# HAP-12xBusverteiler-1_0.net
KiCad netlist of a schematic drawn in EAGLE
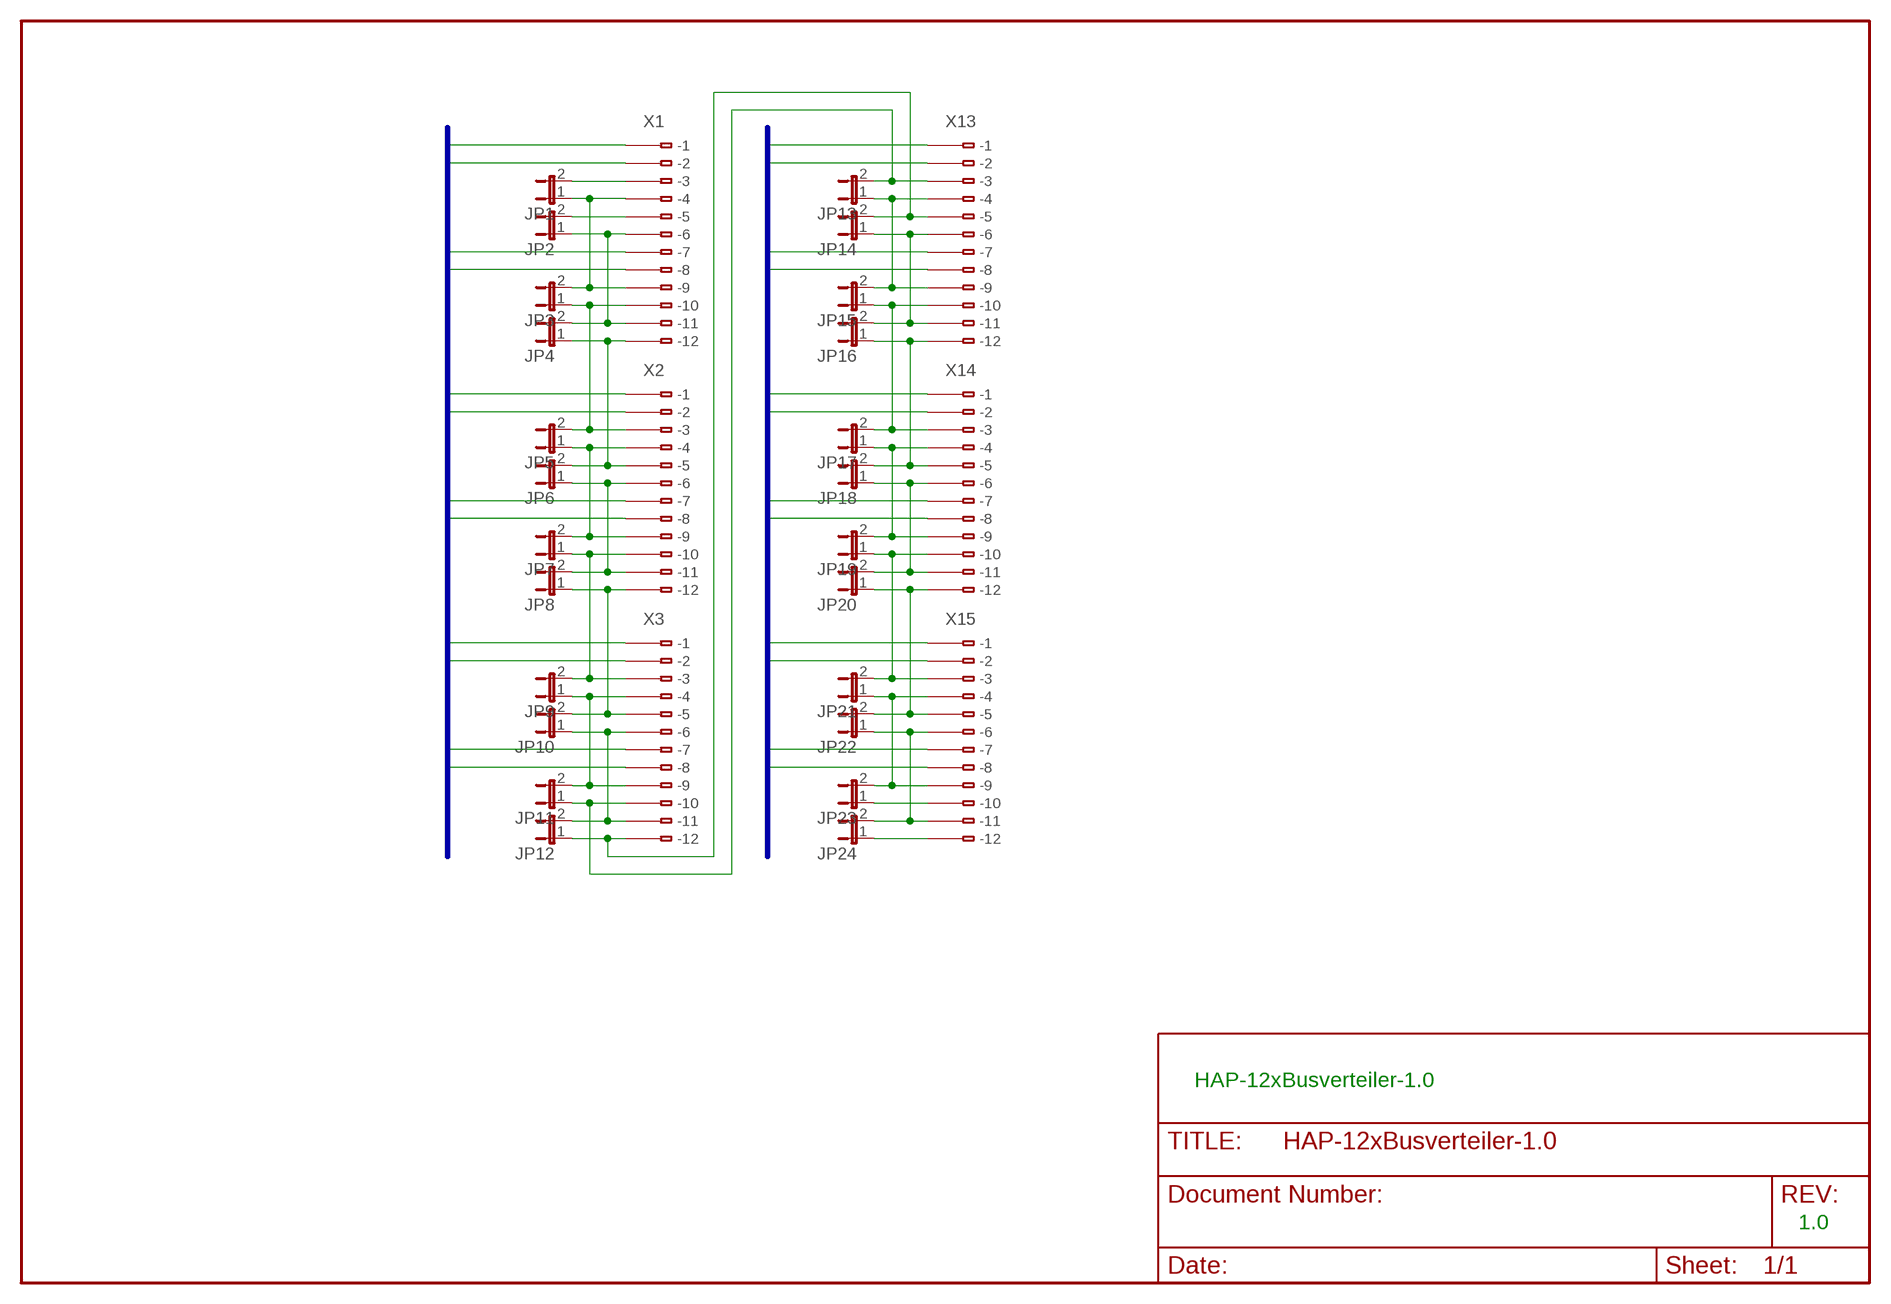
[diagram p0: schematic, sheet 1]

(export (version "E")
  (design (tool "Eeschema 10.0.6"))
  (components
    (comp (ref "JP1")
      (value "JP1E")
      (footprint "eagle-import:JP1")
      (libsource (lib "eagle-import") (part "JP1E"))
    )
    (comp (ref "JP2")
      (value "JP1E")
      (footprint "eagle-import:JP1")
      (libsource (lib "eagle-import") (part "JP1E"))
    )
    (comp (ref "JP3")
      (value "JP1E")
      (footprint "eagle-import:JP1")
      (libsource (lib "eagle-import") (part "JP1E"))
    )
    (comp (ref "JP4")
      (value "JP1E")
      (footprint "eagle-import:JP1")
      (libsource (lib "eagle-import") (part "JP1E"))
    )
    (comp (ref "JP5")
      (value "JP1E")
      (footprint "eagle-import:JP1")
      (libsource (lib "eagle-import") (part "JP1E"))
    )
    (comp (ref "JP6")
      (value "JP1E")
      (footprint "eagle-import:JP1")
      (libsource (lib "eagle-import") (part "JP1E"))
    )
    (comp (ref "JP7")
      (value "JP1E")
      (footprint "eagle-import:JP1")
      (libsource (lib "eagle-import") (part "JP1E"))
    )
    (comp (ref "JP8")
      (value "JP1E")
      (footprint "eagle-import:JP1")
      (libsource (lib "eagle-import") (part "JP1E"))
    )
    (comp (ref "JP9")
      (value "JP1E")
      (footprint "eagle-import:JP1")
      (libsource (lib "eagle-import") (part "JP1E"))
    )
    (comp (ref "JP10")
      (value "JP1E")
      (footprint "eagle-import:JP1")
      (libsource (lib "eagle-import") (part "JP1E"))
    )
    (comp (ref "JP11")
      (value "JP1E")
      (footprint "eagle-import:JP1")
      (libsource (lib "eagle-import") (part "JP1E"))
    )
    (comp (ref "JP12")
      (value "JP1E")
      (footprint "eagle-import:JP1")
      (libsource (lib "eagle-import") (part "JP1E"))
    )
    (comp (ref "JP13")
      (value "JP1E")
      (footprint "eagle-import:JP1")
      (libsource (lib "eagle-import") (part "JP1E"))
    )
    (comp (ref "JP14")
      (value "JP1E")
      (footprint "eagle-import:JP1")
      (libsource (lib "eagle-import") (part "JP1E"))
    )
    (comp (ref "JP15")
      (value "JP1E")
      (footprint "eagle-import:JP1")
      (libsource (lib "eagle-import") (part "JP1E"))
    )
    (comp (ref "JP16")
      (value "JP1E")
      (footprint "eagle-import:JP1")
      (libsource (lib "eagle-import") (part "JP1E"))
    )
    (comp (ref "JP17")
      (value "JP1E")
      (footprint "eagle-import:JP1")
      (libsource (lib "eagle-import") (part "JP1E"))
    )
    (comp (ref "JP18")
      (value "JP1E")
      (footprint "eagle-import:JP1")
      (libsource (lib "eagle-import") (part "JP1E"))
    )
    (comp (ref "JP19")
      (value "JP1E")
      (footprint "eagle-import:JP1")
      (libsource (lib "eagle-import") (part "JP1E"))
    )
    (comp (ref "JP20")
      (value "JP1E")
      (footprint "eagle-import:JP1")
      (libsource (lib "eagle-import") (part "JP1E"))
    )
    (comp (ref "JP21")
      (value "JP1E")
      (footprint "eagle-import:JP1")
      (libsource (lib "eagle-import") (part "JP1E"))
    )
    (comp (ref "JP22")
      (value "JP1E")
      (footprint "eagle-import:JP1")
      (libsource (lib "eagle-import") (part "JP1E"))
    )
    (comp (ref "JP23")
      (value "JP1E")
      (footprint "eagle-import:JP1")
      (libsource (lib "eagle-import") (part "JP1E"))
    )
    (comp (ref "JP24")
      (value "JP1E")
      (footprint "eagle-import:JP1")
      (libsource (lib "eagle-import") (part "JP1E"))
    )
    (comp (ref "X1")
      (value "233-512")
      (footprint "eagle-import:233-512")
      (fields (field (name "MF") "Wago Corporation") (field (name "MPN") "0233-0512"))
      (libsource (lib "eagle-import") (part "233-512"))
    )
    (comp (ref "X2")
      (value "233-512")
      (footprint "eagle-import:233-512")
      (fields (field (name "MF") "Wago Corporation") (field (name "MPN") "0233-0512"))
      (libsource (lib "eagle-import") (part "233-512"))
    )
    (comp (ref "X3")
      (value "233-512")
      (footprint "eagle-import:233-512")
      (fields (field (name "MF") "Wago Corporation") (field (name "MPN") "0233-0512"))
      (libsource (lib "eagle-import") (part "233-512"))
    )
    (comp (ref "X13")
      (value "233-512")
      (footprint "eagle-import:233-512")
      (fields (field (name "MF") "Wago Corporation") (field (name "MPN") "0233-0512"))
      (libsource (lib "eagle-import") (part "233-512"))
    )
    (comp (ref "X14")
      (value "233-512")
      (footprint "eagle-import:233-512")
      (fields (field (name "MF") "Wago Corporation") (field (name "MPN") "0233-0512"))
      (libsource (lib "eagle-import") (part "233-512"))
    )
    (comp (ref "X15")
      (value "233-512")
      (footprint "eagle-import:233-512")
      (fields (field (name "MF") "Wago Corporation") (field (name "MPN") "0233-0512"))
      (libsource (lib "eagle-import") (part "233-512"))
    )
  )
  (nets
    (net (code "1") (name "/12V") (class "Default")
      (node (ref "X1") (pin "B1") (pinfunction "B-1_B1") (pintype "passive"))
      (node (ref "X1") (pin "B7") (pinfunction "B-7_B7") (pintype "passive"))
      (node (ref "X13") (pin "B1") (pinfunction "B-1_B1") (pintype "passive"))
      (node (ref "X13") (pin "B7") (pinfunction "B-7_B7") (pintype "passive"))
      (node (ref "X14") (pin "B1") (pinfunction "B-1_B1") (pintype "passive"))
      (node (ref "X14") (pin "B7") (pinfunction "B-7_B7") (pintype "passive"))
      (node (ref "X15") (pin "B1") (pinfunction "B-1_B1") (pintype "passive"))
      (node (ref "X15") (pin "B7") (pinfunction "B-7_B7") (pintype "passive"))
      (node (ref "X2") (pin "B1") (pinfunction "B-1_B1") (pintype "passive"))
      (node (ref "X2") (pin "B7") (pinfunction "B-7_B7") (pintype "passive"))
      (node (ref "X3") (pin "B1") (pinfunction "B-1_B1") (pintype "passive"))
      (node (ref "X3") (pin "B7") (pinfunction "B-7_B7") (pintype "passive"))
    )
    (net (code "2") (name "/GND") (class "Default")
      (node (ref "X1") (pin "B2") (pinfunction "B-2_B2") (pintype "passive"))
      (node (ref "X1") (pin "B8") (pinfunction "B-8_B8") (pintype "passive"))
      (node (ref "X13") (pin "B2") (pinfunction "B-2_B2") (pintype "passive"))
      (node (ref "X13") (pin "B8") (pinfunction "B-8_B8") (pintype "passive"))
      (node (ref "X14") (pin "B2") (pinfunction "B-2_B2") (pintype "passive"))
      (node (ref "X14") (pin "B8") (pinfunction "B-8_B8") (pintype "passive"))
      (node (ref "X15") (pin "B2") (pinfunction "B-2_B2") (pintype "passive"))
      (node (ref "X15") (pin "B8") (pinfunction "B-8_B8") (pintype "passive"))
      (node (ref "X2") (pin "B2") (pinfunction "B-2_B2") (pintype "passive"))
      (node (ref "X2") (pin "B8") (pinfunction "B-8_B8") (pintype "passive"))
      (node (ref "X3") (pin "B2") (pinfunction "B-2_B2") (pintype "passive"))
      (node (ref "X3") (pin "B8") (pinfunction "B-8_B8") (pintype "passive"))
    )
    (net (code "3") (name "Net-(X1-B-3)") (class "Default")
      (node (ref "JP1") (pin "2") (pinfunction "2_2") (pintype "passive"))
      (node (ref "X1") (pin "B3") (pinfunction "B-3_B3") (pintype "passive"))
    )
    (net (code "4") (name "Net-(X1-B-4)") (class "Default")
      (node (ref "JP1") (pin "1") (pinfunction "1_1") (pintype "passive"))
      (node (ref "JP3") (pin "2") (pinfunction "2_2") (pintype "passive"))
      (node (ref "X1") (pin "B4") (pinfunction "B-4_B4") (pintype "passive"))
      (node (ref "X1") (pin "B9") (pinfunction "B-9_B9") (pintype "passive"))
    )
    (net (code "5") (name "Net-(X1-B-5)") (class "Default")
      (node (ref "JP2") (pin "2") (pinfunction "2_2") (pintype "passive"))
      (node (ref "X1") (pin "B5") (pinfunction "B-5_B5") (pintype "passive"))
    )
    (net (code "6") (name "Net-(X1-B-10)") (class "Default")
      (node (ref "JP3") (pin "1") (pinfunction "1_1") (pintype "passive"))
      (node (ref "JP5") (pin "2") (pinfunction "2_2") (pintype "passive"))
      (node (ref "X1") (pin "B10") (pinfunction "B-10_B10") (pintype "passive"))
      (node (ref "X2") (pin "B3") (pinfunction "B-3_B3") (pintype "passive"))
    )
    (net (code "7") (name "Net-(X1-B-11)") (class "Default")
      (node (ref "JP2") (pin "1") (pinfunction "1_1") (pintype "passive"))
      (node (ref "JP4") (pin "2") (pinfunction "2_2") (pintype "passive"))
      (node (ref "X1") (pin "B11") (pinfunction "B-11_B11") (pintype "passive"))
      (node (ref "X1") (pin "B6") (pinfunction "B-6_B6") (pintype "passive"))
    )
    (net (code "8") (name "Net-(X1-B-12)") (class "Default")
      (node (ref "JP4") (pin "1") (pinfunction "1_1") (pintype "passive"))
      (node (ref "JP6") (pin "2") (pinfunction "2_2") (pintype "passive"))
      (node (ref "X1") (pin "B12") (pinfunction "B-12_B12") (pintype "passive"))
      (node (ref "X2") (pin "B5") (pinfunction "B-5_B5") (pintype "passive"))
    )
    (net (code "9") (name "Net-(X2-B-4)") (class "Default")
      (node (ref "JP5") (pin "1") (pinfunction "1_1") (pintype "passive"))
      (node (ref "JP7") (pin "2") (pinfunction "2_2") (pintype "passive"))
      (node (ref "X2") (pin "B4") (pinfunction "B-4_B4") (pintype "passive"))
      (node (ref "X2") (pin "B9") (pinfunction "B-9_B9") (pintype "passive"))
    )
    (net (code "10") (name "Net-(X2-B-10)") (class "Default")
      (node (ref "JP7") (pin "1") (pinfunction "1_1") (pintype "passive"))
      (node (ref "JP9") (pin "2") (pinfunction "2_2") (pintype "passive"))
      (node (ref "X2") (pin "B10") (pinfunction "B-10_B10") (pintype "passive"))
      (node (ref "X3") (pin "B3") (pinfunction "B-3_B3") (pintype "passive"))
    )
    (net (code "11") (name "Net-(X2-B-11)") (class "Default")
      (node (ref "JP6") (pin "1") (pinfunction "1_1") (pintype "passive"))
      (node (ref "JP8") (pin "2") (pinfunction "2_2") (pintype "passive"))
      (node (ref "X2") (pin "B11") (pinfunction "B-11_B11") (pintype "passive"))
      (node (ref "X2") (pin "B6") (pinfunction "B-6_B6") (pintype "passive"))
    )
    (net (code "12") (name "Net-(X2-B-12)") (class "Default")
      (node (ref "JP10") (pin "2") (pinfunction "2_2") (pintype "passive"))
      (node (ref "JP8") (pin "1") (pinfunction "1_1") (pintype "passive"))
      (node (ref "X2") (pin "B12") (pinfunction "B-12_B12") (pintype "passive"))
      (node (ref "X3") (pin "B5") (pinfunction "B-5_B5") (pintype "passive"))
    )
    (net (code "13") (name "Net-(X3-B-4)") (class "Default")
      (node (ref "JP11") (pin "2") (pinfunction "2_2") (pintype "passive"))
      (node (ref "JP9") (pin "1") (pinfunction "1_1") (pintype "passive"))
      (node (ref "X3") (pin "B4") (pinfunction "B-4_B4") (pintype "passive"))
      (node (ref "X3") (pin "B9") (pinfunction "B-9_B9") (pintype "passive"))
    )
    (net (code "14") (name "Net-(X3-B-11)") (class "Default")
      (node (ref "JP10") (pin "1") (pinfunction "1_1") (pintype "passive"))
      (node (ref "JP12") (pin "2") (pinfunction "2_2") (pintype "passive"))
      (node (ref "X3") (pin "B11") (pinfunction "B-11_B11") (pintype "passive"))
      (node (ref "X3") (pin "B6") (pinfunction "B-6_B6") (pintype "passive"))
    )
    (net (code "15") (name "Net-(X13-B-3)") (class "Default")
      (node (ref "JP11") (pin "1") (pinfunction "1_1") (pintype "passive"))
      (node (ref "JP13") (pin "2") (pinfunction "2_2") (pintype "passive"))
      (node (ref "X13") (pin "B3") (pinfunction "B-3_B3") (pintype "passive"))
      (node (ref "X3") (pin "B10") (pinfunction "B-10_B10") (pintype "passive"))
    )
    (net (code "16") (name "Net-(X13-B-4)") (class "Default")
      (node (ref "JP13") (pin "1") (pinfunction "1_1") (pintype "passive"))
      (node (ref "JP15") (pin "2") (pinfunction "2_2") (pintype "passive"))
      (node (ref "X13") (pin "B4") (pinfunction "B-4_B4") (pintype "passive"))
      (node (ref "X13") (pin "B9") (pinfunction "B-9_B9") (pintype "passive"))
    )
    (net (code "17") (name "Net-(X13-B-5)") (class "Default")
      (node (ref "JP12") (pin "1") (pinfunction "1_1") (pintype "passive"))
      (node (ref "JP14") (pin "2") (pinfunction "2_2") (pintype "passive"))
      (node (ref "X13") (pin "B5") (pinfunction "B-5_B5") (pintype "passive"))
      (node (ref "X3") (pin "B12") (pinfunction "B-12_B12") (pintype "passive"))
    )
    (net (code "18") (name "Net-(X13-B-10)") (class "Default")
      (node (ref "JP15") (pin "1") (pinfunction "1_1") (pintype "passive"))
      (node (ref "JP17") (pin "2") (pinfunction "2_2") (pintype "passive"))
      (node (ref "X13") (pin "B10") (pinfunction "B-10_B10") (pintype "passive"))
      (node (ref "X14") (pin "B3") (pinfunction "B-3_B3") (pintype "passive"))
    )
    (net (code "19") (name "Net-(X13-B-11)") (class "Default")
      (node (ref "JP14") (pin "1") (pinfunction "1_1") (pintype "passive"))
      (node (ref "JP16") (pin "2") (pinfunction "2_2") (pintype "passive"))
      (node (ref "X13") (pin "B11") (pinfunction "B-11_B11") (pintype "passive"))
      (node (ref "X13") (pin "B6") (pinfunction "B-6_B6") (pintype "passive"))
    )
    (net (code "20") (name "Net-(X13-B-12)") (class "Default")
      (node (ref "JP16") (pin "1") (pinfunction "1_1") (pintype "passive"))
      (node (ref "JP18") (pin "2") (pinfunction "2_2") (pintype "passive"))
      (node (ref "X13") (pin "B12") (pinfunction "B-12_B12") (pintype "passive"))
      (node (ref "X14") (pin "B5") (pinfunction "B-5_B5") (pintype "passive"))
    )
    (net (code "21") (name "Net-(X14-B-4)") (class "Default")
      (node (ref "JP17") (pin "1") (pinfunction "1_1") (pintype "passive"))
      (node (ref "JP19") (pin "2") (pinfunction "2_2") (pintype "passive"))
      (node (ref "X14") (pin "B4") (pinfunction "B-4_B4") (pintype "passive"))
      (node (ref "X14") (pin "B9") (pinfunction "B-9_B9") (pintype "passive"))
    )
    (net (code "22") (name "Net-(X14-B-10)") (class "Default")
      (node (ref "JP19") (pin "1") (pinfunction "1_1") (pintype "passive"))
      (node (ref "JP21") (pin "2") (pinfunction "2_2") (pintype "passive"))
      (node (ref "X14") (pin "B10") (pinfunction "B-10_B10") (pintype "passive"))
      (node (ref "X15") (pin "B3") (pinfunction "B-3_B3") (pintype "passive"))
    )
    (net (code "23") (name "Net-(X14-B-11)") (class "Default")
      (node (ref "JP18") (pin "1") (pinfunction "1_1") (pintype "passive"))
      (node (ref "JP20") (pin "2") (pinfunction "2_2") (pintype "passive"))
      (node (ref "X14") (pin "B11") (pinfunction "B-11_B11") (pintype "passive"))
      (node (ref "X14") (pin "B6") (pinfunction "B-6_B6") (pintype "passive"))
    )
    (net (code "24") (name "Net-(X14-B-12)") (class "Default")
      (node (ref "JP20") (pin "1") (pinfunction "1_1") (pintype "passive"))
      (node (ref "JP22") (pin "2") (pinfunction "2_2") (pintype "passive"))
      (node (ref "X14") (pin "B12") (pinfunction "B-12_B12") (pintype "passive"))
      (node (ref "X15") (pin "B5") (pinfunction "B-5_B5") (pintype "passive"))
    )
    (net (code "25") (name "Net-(X15-B-4)") (class "Default")
      (node (ref "JP21") (pin "1") (pinfunction "1_1") (pintype "passive"))
      (node (ref "JP23") (pin "2") (pinfunction "2_2") (pintype "passive"))
      (node (ref "X15") (pin "B4") (pinfunction "B-4_B4") (pintype "passive"))
      (node (ref "X15") (pin "B9") (pinfunction "B-9_B9") (pintype "passive"))
    )
    (net (code "26") (name "Net-(X15-B-10)") (class "Default")
      (node (ref "JP23") (pin "1") (pinfunction "1_1") (pintype "passive"))
      (node (ref "X15") (pin "B10") (pinfunction "B-10_B10") (pintype "passive"))
    )
    (net (code "27") (name "Net-(X15-B-11)") (class "Default")
      (node (ref "JP22") (pin "1") (pinfunction "1_1") (pintype "passive"))
      (node (ref "JP24") (pin "2") (pinfunction "2_2") (pintype "passive"))
      (node (ref "X15") (pin "B11") (pinfunction "B-11_B11") (pintype "passive"))
      (node (ref "X15") (pin "B6") (pinfunction "B-6_B6") (pintype "passive"))
    )
    (net (code "28") (name "Net-(X15-B-12)") (class "Default")
      (node (ref "JP24") (pin "1") (pinfunction "1_1") (pintype "passive"))
      (node (ref "X15") (pin "B12") (pinfunction "B-12_B12") (pintype "passive"))
    )
    (net (code "29") (name "unconnected-(X1--1-PadA1)") (class "Default")
      (node (ref "X1") (pin "A1") (pinfunction "-1_A1") (pintype "passive"))
    )
    (net (code "30") (name "unconnected-(X1--2-PadA2)") (class "Default")
      (node (ref "X1") (pin "A2") (pinfunction "-2_A2") (pintype "passive"))
    )
    (net (code "31") (name "unconnected-(X1--3-PadA3)") (class "Default")
      (node (ref "X1") (pin "A3") (pinfunction "-3_A3") (pintype "passive"))
    )
    (net (code "32") (name "unconnected-(X1--4-PadA4)") (class "Default")
      (node (ref "X1") (pin "A4") (pinfunction "-4_A4") (pintype "passive"))
    )
    (net (code "33") (name "unconnected-(X1--5-PadA5)") (class "Default")
      (node (ref "X1") (pin "A5") (pinfunction "-5_A5") (pintype "passive"))
    )
    (net (code "34") (name "unconnected-(X1--6-PadA6)") (class "Default")
      (node (ref "X1") (pin "A6") (pinfunction "-6_A6") (pintype "passive"))
    )
    (net (code "35") (name "unconnected-(X1--7-PadA7)") (class "Default")
      (node (ref "X1") (pin "A7") (pinfunction "-7_A7") (pintype "passive"))
    )
    (net (code "36") (name "unconnected-(X1--8-PadA8)") (class "Default")
      (node (ref "X1") (pin "A8") (pinfunction "-8_A8") (pintype "passive"))
    )
    (net (code "37") (name "unconnected-(X1--9-PadA9)") (class "Default")
      (node (ref "X1") (pin "A9") (pinfunction "-9_A9") (pintype "passive"))
    )
    (net (code "38") (name "unconnected-(X1--10-PadA10)") (class "Default")
      (node (ref "X1") (pin "A10") (pinfunction "-10_A10") (pintype "passive"))
    )
    (net (code "39") (name "unconnected-(X1--11-PadA11)") (class "Default")
      (node (ref "X1") (pin "A11") (pinfunction "-11_A11") (pintype "passive"))
    )
    (net (code "40") (name "unconnected-(X1--12-PadA12)") (class "Default")
      (node (ref "X1") (pin "A12") (pinfunction "-12_A12") (pintype "passive"))
    )
    (net (code "41") (name "unconnected-(X2--1-PadA1)") (class "Default")
      (node (ref "X2") (pin "A1") (pinfunction "-1_A1") (pintype "passive"))
    )
    (net (code "42") (name "unconnected-(X2--2-PadA2)") (class "Default")
      (node (ref "X2") (pin "A2") (pinfunction "-2_A2") (pintype "passive"))
    )
    (net (code "43") (name "unconnected-(X2--3-PadA3)") (class "Default")
      (node (ref "X2") (pin "A3") (pinfunction "-3_A3") (pintype "passive"))
    )
    (net (code "44") (name "unconnected-(X2--4-PadA4)") (class "Default")
      (node (ref "X2") (pin "A4") (pinfunction "-4_A4") (pintype "passive"))
    )
    (net (code "45") (name "unconnected-(X2--5-PadA5)") (class "Default")
      (node (ref "X2") (pin "A5") (pinfunction "-5_A5") (pintype "passive"))
    )
    (net (code "46") (name "unconnected-(X2--6-PadA6)") (class "Default")
      (node (ref "X2") (pin "A6") (pinfunction "-6_A6") (pintype "passive"))
    )
    (net (code "47") (name "unconnected-(X2--7-PadA7)") (class "Default")
      (node (ref "X2") (pin "A7") (pinfunction "-7_A7") (pintype "passive"))
    )
    (net (code "48") (name "unconnected-(X2--8-PadA8)") (class "Default")
      (node (ref "X2") (pin "A8") (pinfunction "-8_A8") (pintype "passive"))
    )
    (net (code "49") (name "unconnected-(X2--9-PadA9)") (class "Default")
      (node (ref "X2") (pin "A9") (pinfunction "-9_A9") (pintype "passive"))
    )
    (net (code "50") (name "unconnected-(X2--10-PadA10)") (class "Default")
      (node (ref "X2") (pin "A10") (pinfunction "-10_A10") (pintype "passive"))
    )
    (net (code "51") (name "unconnected-(X2--11-PadA11)") (class "Default")
      (node (ref "X2") (pin "A11") (pinfunction "-11_A11") (pintype "passive"))
    )
    (net (code "52") (name "unconnected-(X2--12-PadA12)") (class "Default")
      (node (ref "X2") (pin "A12") (pinfunction "-12_A12") (pintype "passive"))
    )
    (net (code "53") (name "unconnected-(X3--1-PadA1)") (class "Default")
      (node (ref "X3") (pin "A1") (pinfunction "-1_A1") (pintype "passive"))
    )
    (net (code "54") (name "unconnected-(X3--2-PadA2)") (class "Default")
      (node (ref "X3") (pin "A2") (pinfunction "-2_A2") (pintype "passive"))
    )
    (net (code "55") (name "unconnected-(X3--3-PadA3)") (class "Default")
      (node (ref "X3") (pin "A3") (pinfunction "-3_A3") (pintype "passive"))
    )
    (net (code "56") (name "unconnected-(X3--4-PadA4)") (class "Default")
      (node (ref "X3") (pin "A4") (pinfunction "-4_A4") (pintype "passive"))
    )
    (net (code "57") (name "unconnected-(X3--5-PadA5)") (class "Default")
      (node (ref "X3") (pin "A5") (pinfunction "-5_A5") (pintype "passive"))
    )
    (net (code "58") (name "unconnected-(X3--6-PadA6)") (class "Default")
      (node (ref "X3") (pin "A6") (pinfunction "-6_A6") (pintype "passive"))
    )
    (net (code "59") (name "unconnected-(X3--7-PadA7)") (class "Default")
      (node (ref "X3") (pin "A7") (pinfunction "-7_A7") (pintype "passive"))
    )
    (net (code "60") (name "unconnected-(X3--8-PadA8)") (class "Default")
      (node (ref "X3") (pin "A8") (pinfunction "-8_A8") (pintype "passive"))
    )
    (net (code "61") (name "unconnected-(X3--9-PadA9)") (class "Default")
      (node (ref "X3") (pin "A9") (pinfunction "-9_A9") (pintype "passive"))
    )
    (net (code "62") (name "unconnected-(X3--10-PadA10)") (class "Default")
      (node (ref "X3") (pin "A10") (pinfunction "-10_A10") (pintype "passive"))
    )
    (net (code "63") (name "unconnected-(X3--11-PadA11)") (class "Default")
      (node (ref "X3") (pin "A11") (pinfunction "-11_A11") (pintype "passive"))
    )
    (net (code "64") (name "unconnected-(X3--12-PadA12)") (class "Default")
      (node (ref "X3") (pin "A12") (pinfunction "-12_A12") (pintype "passive"))
    )
    (net (code "65") (name "unconnected-(X13--1-PadA1)") (class "Default")
      (node (ref "X13") (pin "A1") (pinfunction "-1_A1") (pintype "passive"))
    )
    (net (code "66") (name "unconnected-(X13--2-PadA2)") (class "Default")
      (node (ref "X13") (pin "A2") (pinfunction "-2_A2") (pintype "passive"))
    )
    (net (code "67") (name "unconnected-(X13--3-PadA3)") (class "Default")
      (node (ref "X13") (pin "A3") (pinfunction "-3_A3") (pintype "passive"))
    )
    (net (code "68") (name "unconnected-(X13--4-PadA4)") (class "Default")
      (node (ref "X13") (pin "A4") (pinfunction "-4_A4") (pintype "passive"))
    )
    (net (code "69") (name "unconnected-(X13--5-PadA5)") (class "Default")
      (node (ref "X13") (pin "A5") (pinfunction "-5_A5") (pintype "passive"))
    )
    (net (code "70") (name "unconnected-(X13--6-PadA6)") (class "Default")
      (node (ref "X13") (pin "A6") (pinfunction "-6_A6") (pintype "passive"))
    )
    (net (code "71") (name "unconnected-(X13--7-PadA7)") (class "Default")
      (node (ref "X13") (pin "A7") (pinfunction "-7_A7") (pintype "passive"))
    )
    (net (code "72") (name "unconnected-(X13--8-PadA8)") (class "Default")
      (node (ref "X13") (pin "A8") (pinfunction "-8_A8") (pintype "passive"))
    )
    (net (code "73") (name "unconnected-(X13--9-PadA9)") (class "Default")
      (node (ref "X13") (pin "A9") (pinfunction "-9_A9") (pintype "passive"))
    )
    (net (code "74") (name "unconnected-(X13--10-PadA10)") (class "Default")
      (node (ref "X13") (pin "A10") (pinfunction "-10_A10") (pintype "passive"))
    )
    (net (code "75") (name "unconnected-(X13--11-PadA11)") (class "Default")
      (node (ref "X13") (pin "A11") (pinfunction "-11_A11") (pintype "passive"))
    )
    (net (code "76") (name "unconnected-(X13--12-PadA12)") (class "Default")
      (node (ref "X13") (pin "A12") (pinfunction "-12_A12") (pintype "passive"))
    )
    (net (code "77") (name "unconnected-(X14--1-PadA1)") (class "Default")
      (node (ref "X14") (pin "A1") (pinfunction "-1_A1") (pintype "passive"))
    )
    (net (code "78") (name "unconnected-(X14--2-PadA2)") (class "Default")
      (node (ref "X14") (pin "A2") (pinfunction "-2_A2") (pintype "passive"))
    )
    (net (code "79") (name "unconnected-(X14--3-PadA3)") (class "Default")
      (node (ref "X14") (pin "A3") (pinfunction "-3_A3") (pintype "passive"))
    )
    (net (code "80") (name "unconnected-(X14--4-PadA4)") (class "Default")
      (node (ref "X14") (pin "A4") (pinfunction "-4_A4") (pintype "passive"))
    )
    (net (code "81") (name "unconnected-(X14--5-PadA5)") (class "Default")
      (node (ref "X14") (pin "A5") (pinfunction "-5_A5") (pintype "passive"))
    )
    (net (code "82") (name "unconnected-(X14--6-PadA6)") (class "Default")
      (node (ref "X14") (pin "A6") (pinfunction "-6_A6") (pintype "passive"))
    )
    (net (code "83") (name "unconnected-(X14--7-PadA7)") (class "Default")
      (node (ref "X14") (pin "A7") (pinfunction "-7_A7") (pintype "passive"))
    )
    (net (code "84") (name "unconnected-(X14--8-PadA8)") (class "Default")
      (node (ref "X14") (pin "A8") (pinfunction "-8_A8") (pintype "passive"))
    )
    (net (code "85") (name "unconnected-(X14--9-PadA9)") (class "Default")
      (node (ref "X14") (pin "A9") (pinfunction "-9_A9") (pintype "passive"))
    )
    (net (code "86") (name "unconnected-(X14--10-PadA10)") (class "Default")
      (node (ref "X14") (pin "A10") (pinfunction "-10_A10") (pintype "passive"))
    )
    (net (code "87") (name "unconnected-(X14--11-PadA11)") (class "Default")
      (node (ref "X14") (pin "A11") (pinfunction "-11_A11") (pintype "passive"))
    )
    (net (code "88") (name "unconnected-(X14--12-PadA12)") (class "Default")
      (node (ref "X14") (pin "A12") (pinfunction "-12_A12") (pintype "passive"))
    )
    (net (code "89") (name "unconnected-(X15--1-PadA1)") (class "Default")
      (node (ref "X15") (pin "A1") (pinfunction "-1_A1") (pintype "passive"))
    )
    (net (code "90") (name "unconnected-(X15--2-PadA2)") (class "Default")
      (node (ref "X15") (pin "A2") (pinfunction "-2_A2") (pintype "passive"))
    )
    (net (code "91") (name "unconnected-(X15--3-PadA3)") (class "Default")
      (node (ref "X15") (pin "A3") (pinfunction "-3_A3") (pintype "passive"))
    )
    (net (code "92") (name "unconnected-(X15--4-PadA4)") (class "Default")
      (node (ref "X15") (pin "A4") (pinfunction "-4_A4") (pintype "passive"))
    )
    (net (code "93") (name "unconnected-(X15--5-PadA5)") (class "Default")
      (node (ref "X15") (pin "A5") (pinfunction "-5_A5") (pintype "passive"))
    )
    (net (code "94") (name "unconnected-(X15--6-PadA6)") (class "Default")
      (node (ref "X15") (pin "A6") (pinfunction "-6_A6") (pintype "passive"))
    )
    (net (code "95") (name "unconnected-(X15--7-PadA7)") (class "Default")
      (node (ref "X15") (pin "A7") (pinfunction "-7_A7") (pintype "passive"))
    )
    (net (code "96") (name "unconnected-(X15--8-PadA8)") (class "Default")
      (node (ref "X15") (pin "A8") (pinfunction "-8_A8") (pintype "passive"))
    )
    (net (code "97") (name "unconnected-(X15--9-PadA9)") (class "Default")
      (node (ref "X15") (pin "A9") (pinfunction "-9_A9") (pintype "passive"))
    )
    (net (code "98") (name "unconnected-(X15--10-PadA10)") (class "Default")
      (node (ref "X15") (pin "A10") (pinfunction "-10_A10") (pintype "passive"))
    )
    (net (code "99") (name "unconnected-(X15--11-PadA11)") (class "Default")
      (node (ref "X15") (pin "A11") (pinfunction "-11_A11") (pintype "passive"))
    )
    (net (code "100") (name "unconnected-(X15--12-PadA12)") (class "Default")
      (node (ref "X15") (pin "A12") (pinfunction "-12_A12") (pintype "passive"))
    )
  )
)
